# DCDC_4805.net
KiCad netlist of a schematic drawn in Altium Designer
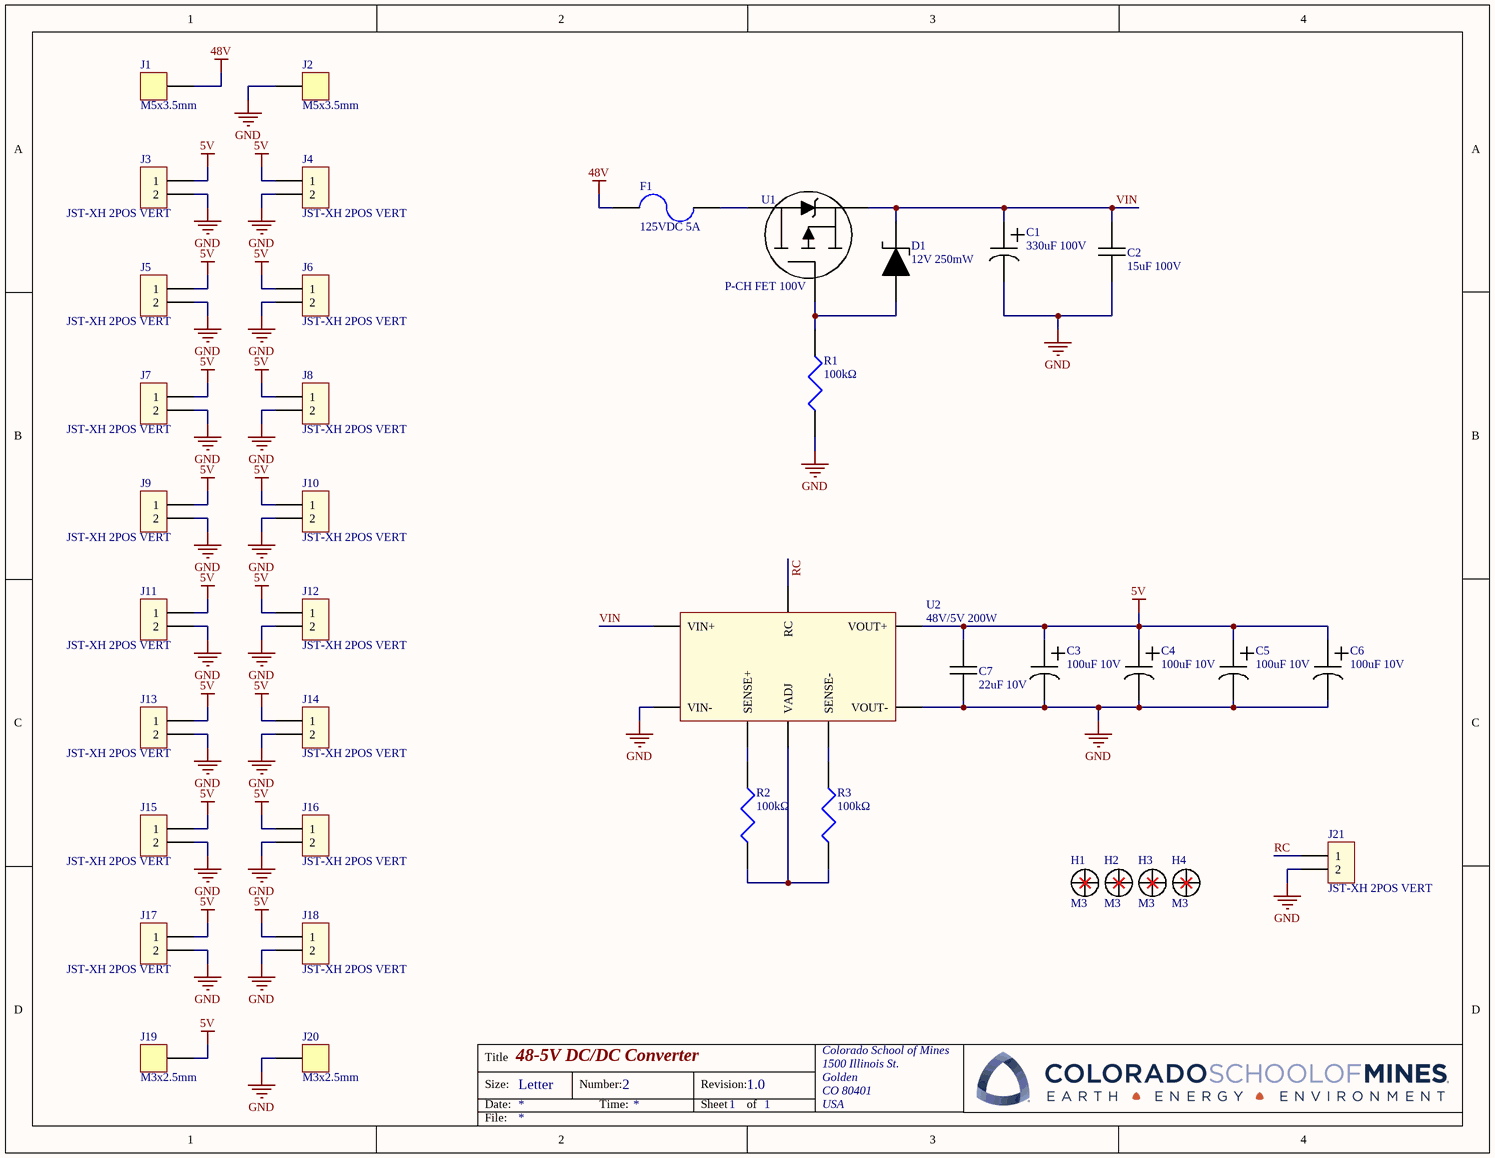
[diagram p0: DCDC_4805.SchDoc]

(export (version "E")
  (design (tool "Eeschema 10.0.6"))
  (components
    (comp (ref "C1")
      (value "330uF 100V")
      (footprint "EEV-FK2A331M")
      (description "Panasonic CAP ALUM 330UF 20% 100V SMD")
      (fields
        (field (name "PART NUMBER") "EEV-FK2A331M")
        (field (name "MANUFACTURER") "Panasonic Electronic Components")
      )
      (libsource (lib "MinesROV") (part "EEV-FK2A331M"))
    )
    (comp (ref "C2")
      (value "15uF 100V")
      (footprint "C2220M Generic")
      (description "TDK CAP CER 15UF 100V X7S 2220")
      (fields
        (field (name "PART NUMBER") "C5750X7S2A156M250KB")
        (field (name "MANUFACTURER") "TDK Corporation")
      )
      (libsource (lib "MinesROV") (part "C5750X7S2A156M250KB"))
    )
    (comp (ref "C3")
      (value "100uF 10V")
      (footprint "865080243007")
      (description "Wurth CAP ALUM POLY 100UF 20% 10V SMD")
      (fields (field (name "PART NUMBER") "865080243007") (field (name "MANUFACTURER") "Würth Elektronik"))
      (libsource (lib "MinesROV") (part "865080243007"))
    )
    (comp (ref "C4")
      (value "100uF 10V")
      (footprint "865080243007")
      (description "Wurth CAP ALUM POLY 100UF 20% 10V SMD")
      (fields (field (name "PART NUMBER") "865080243007") (field (name "MANUFACTURER") "Würth Elektronik"))
      (libsource (lib "MinesROV") (part "865080243007"))
    )
    (comp (ref "C5")
      (value "100uF 10V")
      (footprint "865080243007")
      (description "Wurth CAP ALUM POLY 100UF 20% 10V SMD")
      (fields (field (name "PART NUMBER") "865080243007") (field (name "MANUFACTURER") "Würth Elektronik"))
      (libsource (lib "MinesROV") (part "865080243007"))
    )
    (comp (ref "C6")
      (value "100uF 10V")
      (footprint "865080243007")
      (description "Wurth CAP ALUM POLY 100UF 20% 10V SMD")
      (fields (field (name "PART NUMBER") "865080243007") (field (name "MANUFACTURER") "Würth Elektronik"))
      (libsource (lib "MinesROV") (part "865080243007"))
    )
    (comp (ref "C7")
      (value "22uF 10V")
      (footprint "885012107011")
      (description "Wurth CAP CER 22UF 10V X5R 0805")
      (fields (field (name "PART NUMBER") "885012107011") (field (name "MANUFACTURER") "Würth Elektronik"))
      (libsource (lib "MinesROV") (part "885012107011"))
    )
    (comp (ref "D1")
      (value "12V 250mW")
      (footprint "BZX84-C12,235")
      (description "Nexperia DIODE ZENER 12V 250MW TO236AB")
      (fields (field (name "PART NUMBER") "BZX84-C12,235") (field (name "MANUFACTURER") "Nexperia"))
      (libsource (lib "MinesROV") (part "BZX84-C12,235"))
    )
    (comp (ref "F1")
      (value "125VDC 5A")
      (footprint "0154005.DRL")
      (description "Littelfuse FUSE BRD MNT 5A 125VAC/VDC 2SMD")
      (fields (field (name "MANUFACTURER") "Littelfuse") (field (name "PART NUMBER") "0456030.ER0154005.DRL"))
      (libsource (lib "MinesROV") (part "0154005.DRL"))
    )
    (comp (ref "H1")
      (value "M3")
      (footprint "M3_MOUNTING_HOLE")
      (description "MECHANICAL M3 Mounting Hole")
      (libsource (lib "MinesROV") (part "M3_Mounting_Hole"))
    )
    (comp (ref "H2")
      (value "M3")
      (footprint "M3_MOUNTING_HOLE")
      (description "MECHANICAL M3 Mounting Hole")
      (libsource (lib "MinesROV") (part "M3_Mounting_Hole"))
    )
    (comp (ref "H3")
      (value "M3")
      (footprint "M3_MOUNTING_HOLE")
      (description "MECHANICAL M3 Mounting Hole")
      (libsource (lib "MinesROV") (part "M3_Mounting_Hole"))
    )
    (comp (ref "H4")
      (value "M3")
      (footprint "M3_MOUNTING_HOLE")
      (description "MECHANICAL M3 Mounting Hole")
      (libsource (lib "MinesROV") (part "M3_Mounting_Hole"))
    )
    (comp (ref "J1")
      (value "M5x3.5mm")
      (footprint "74655095")
      (description "Wurth WP-THRBU REDCUBE THR internal through-hole thread, 10x10mm, M5x3.5mm, 8 pins, 85A")
      (fields
        (field (name "PART NUMBER") "74655095R")
        (field (name "MANUFACTURER") "Wurth Elektronik")
        (field (name "PUBLISHER") "Wurth Elektronik")
      )
      (libsource (lib "") (part "74655095R_1"))
    )
    (comp (ref "J2")
      (value "M5x3.5mm")
      (footprint "74655095")
      (description "Wurth WP-THRBU REDCUBE THR internal through-hole thread, 10x10mm, M5x3.5mm, 8 pins, 85A")
      (fields
        (field (name "PART NUMBER") "74655095R")
        (field (name "MANUFACTURER") "Wurth Elektronik")
        (field (name "PUBLISHER") "Wurth Elektronik")
      )
      (libsource (lib "MinesROV") (part "74655095R"))
    )
    (comp (ref "J3")
      (value "JST-XH 2POS VERT")
      (footprint "FP-B2B-XH-A_LF_SN-MFG")
      (description "JST XH CONN HEADER VERT 2POS 2.5MM")
      (fields (field (name "MANUFACTURER") "JST") (field (name "PART NUMBER") "B2B-XH-A(LF)(SN)"))
      (libsource (lib "MinesROV") (part "B2B-XH-A(LF)(SN)"))
    )
    (comp (ref "J4")
      (value "JST-XH 2POS VERT")
      (footprint "FP-B2B-XH-A_LF_SN-MFG")
      (description "JST XH CONN HEADER VERT 2POS 2.5MM")
      (fields (field (name "MANUFACTURER") "JST") (field (name "PART NUMBER") "B2B-XH-A(LF)(SN)"))
      (libsource (lib "") (part "B2B-XH-A(LF)(SN)_1"))
    )
    (comp (ref "J5")
      (value "JST-XH 2POS VERT")
      (footprint "FP-B2B-XH-A_LF_SN-MFG")
      (description "JST XH CONN HEADER VERT 2POS 2.5MM")
      (fields (field (name "MANUFACTURER") "JST") (field (name "PART NUMBER") "B2B-XH-A(LF)(SN)"))
      (libsource (lib "MinesROV") (part "B2B-XH-A(LF)(SN)"))
    )
    (comp (ref "J6")
      (value "JST-XH 2POS VERT")
      (footprint "FP-B2B-XH-A_LF_SN-MFG")
      (description "JST XH CONN HEADER VERT 2POS 2.5MM")
      (fields (field (name "MANUFACTURER") "JST") (field (name "PART NUMBER") "B2B-XH-A(LF)(SN)"))
      (libsource (lib "") (part "B2B-XH-A(LF)(SN)_1"))
    )
    (comp (ref "J7")
      (value "JST-XH 2POS VERT")
      (footprint "FP-B2B-XH-A_LF_SN-MFG")
      (description "JST XH CONN HEADER VERT 2POS 2.5MM")
      (fields (field (name "MANUFACTURER") "JST") (field (name "PART NUMBER") "B2B-XH-A(LF)(SN)"))
      (libsource (lib "MinesROV") (part "B2B-XH-A(LF)(SN)"))
    )
    (comp (ref "J8")
      (value "JST-XH 2POS VERT")
      (footprint "FP-B2B-XH-A_LF_SN-MFG")
      (description "JST XH CONN HEADER VERT 2POS 2.5MM")
      (fields (field (name "MANUFACTURER") "JST") (field (name "PART NUMBER") "B2B-XH-A(LF)(SN)"))
      (libsource (lib "") (part "B2B-XH-A(LF)(SN)_1"))
    )
    (comp (ref "J9")
      (value "JST-XH 2POS VERT")
      (footprint "FP-B2B-XH-A_LF_SN-MFG")
      (description "JST XH CONN HEADER VERT 2POS 2.5MM")
      (fields (field (name "MANUFACTURER") "JST") (field (name "PART NUMBER") "B2B-XH-A(LF)(SN)"))
      (libsource (lib "MinesROV") (part "B2B-XH-A(LF)(SN)"))
    )
    (comp (ref "J10")
      (value "JST-XH 2POS VERT")
      (footprint "FP-B2B-XH-A_LF_SN-MFG")
      (description "JST XH CONN HEADER VERT 2POS 2.5MM")
      (fields (field (name "MANUFACTURER") "JST") (field (name "PART NUMBER") "B2B-XH-A(LF)(SN)"))
      (libsource (lib "") (part "B2B-XH-A(LF)(SN)_1"))
    )
    (comp (ref "J11")
      (value "JST-XH 2POS VERT")
      (footprint "FP-B2B-XH-A_LF_SN-MFG")
      (description "JST XH CONN HEADER VERT 2POS 2.5MM")
      (fields (field (name "MANUFACTURER") "JST") (field (name "PART NUMBER") "B2B-XH-A(LF)(SN)"))
      (libsource (lib "MinesROV") (part "B2B-XH-A(LF)(SN)"))
    )
    (comp (ref "J12")
      (value "JST-XH 2POS VERT")
      (footprint "FP-B2B-XH-A_LF_SN-MFG")
      (description "JST XH CONN HEADER VERT 2POS 2.5MM")
      (fields (field (name "MANUFACTURER") "JST") (field (name "PART NUMBER") "B2B-XH-A(LF)(SN)"))
      (libsource (lib "") (part "B2B-XH-A(LF)(SN)_1"))
    )
    (comp (ref "J13")
      (value "JST-XH 2POS VERT")
      (footprint "FP-B2B-XH-A_LF_SN-MFG")
      (description "JST XH CONN HEADER VERT 2POS 2.5MM")
      (fields (field (name "MANUFACTURER") "JST") (field (name "PART NUMBER") "B2B-XH-A(LF)(SN)"))
      (libsource (lib "MinesROV") (part "B2B-XH-A(LF)(SN)"))
    )
    (comp (ref "J14")
      (value "JST-XH 2POS VERT")
      (footprint "FP-B2B-XH-A_LF_SN-MFG")
      (description "JST XH CONN HEADER VERT 2POS 2.5MM")
      (fields (field (name "MANUFACTURER") "JST") (field (name "PART NUMBER") "B2B-XH-A(LF)(SN)"))
      (libsource (lib "") (part "B2B-XH-A(LF)(SN)_1"))
    )
    (comp (ref "J15")
      (value "JST-XH 2POS VERT")
      (footprint "FP-B2B-XH-A_LF_SN-MFG")
      (description "JST XH CONN HEADER VERT 2POS 2.5MM")
      (fields (field (name "MANUFACTURER") "JST") (field (name "PART NUMBER") "B2B-XH-A(LF)(SN)"))
      (libsource (lib "MinesROV") (part "B2B-XH-A(LF)(SN)"))
    )
    (comp (ref "J16")
      (value "JST-XH 2POS VERT")
      (footprint "FP-B2B-XH-A_LF_SN-MFG")
      (description "JST XH CONN HEADER VERT 2POS 2.5MM")
      (fields (field (name "MANUFACTURER") "JST") (field (name "PART NUMBER") "B2B-XH-A(LF)(SN)"))
      (libsource (lib "") (part "B2B-XH-A(LF)(SN)_1"))
    )
    (comp (ref "J17")
      (value "JST-XH 2POS VERT")
      (footprint "FP-B2B-XH-A_LF_SN-MFG")
      (description "JST XH CONN HEADER VERT 2POS 2.5MM")
      (fields (field (name "MANUFACTURER") "JST") (field (name "PART NUMBER") "B2B-XH-A(LF)(SN)"))
      (libsource (lib "MinesROV") (part "B2B-XH-A(LF)(SN)"))
    )
    (comp (ref "J18")
      (value "JST-XH 2POS VERT")
      (footprint "FP-B2B-XH-A_LF_SN-MFG")
      (description "JST XH CONN HEADER VERT 2POS 2.5MM")
      (fields (field (name "MANUFACTURER") "JST") (field (name "PART NUMBER") "B2B-XH-A(LF)(SN)"))
      (libsource (lib "") (part "B2B-XH-A(LF)(SN)_1"))
    )
    (comp (ref "J19")
      (value "M3x2.5mm")
      (footprint "74650073")
      (description "Wurth WP-THRBU REDCUBE THR internal through-hole thread, 7x7mm, M3x2.5mm, 4 pins, 50A")
      (fields
        (field (name "PART NUMBER") "74650073R")
        (field (name "MANUFACTURER") "Wurth Elektronik")
        (field (name "PUBLISHER") "Wurth Elektronik")
      )
      (libsource (lib "") (part "74650073R_1"))
    )
    (comp (ref "J20")
      (value "M3x2.5mm")
      (footprint "74650073")
      (description "Wurth WP-THRBU REDCUBE THR internal through-hole thread, 7x7mm, M3x2.5mm, 4 pins, 50A")
      (fields
        (field (name "PART NUMBER") "74650073R")
        (field (name "MANUFACTURER") "Wurth Elektronik")
        (field (name "PUBLISHER") "Wurth Elektronik")
      )
      (libsource (lib "MinesROV") (part "74650073R"))
    )
    (comp (ref "J21")
      (value "JST-XH 2POS VERT")
      (footprint "FP-B2B-XH-A_LF_SN-MFG")
      (description "JST XH CONN HEADER VERT 2POS 2.5MM")
      (fields (field (name "MANUFACTURER") "JST") (field (name "PART NUMBER") "B2B-XH-A(LF)(SN)"))
      (libsource (lib "") (part "B2B-XH-A(LF)(SN)_1"))
    )
    (comp (ref "R1")
      (value "100kΩ")
      (footprint "RMCF0805")
      (description "Stackpole RES 100K OHM 1% 1/8W 0805")
      (fields
        (field (name "PART NUMBER") "RMCF0805FT100K")
        (field (name "MANUFACTURER") "Stackpole Electronics Inc")
      )
      (libsource (lib "MinesROV") (part "RMCF0805FT100K"))
    )
    (comp (ref "R2")
      (value "100kΩ")
      (footprint "RMCF0805")
      (description "Stackpole RES 100K OHM 1% 1/8W 0805")
      (fields
        (field (name "PART NUMBER") "RMCF0805FT100K")
        (field (name "MANUFACTURER") "Stackpole Electronics Inc")
      )
      (libsource (lib "MinesROV") (part "RMCF0805FT100K"))
    )
    (comp (ref "R3")
      (value "100kΩ")
      (footprint "RMCF0805")
      (description "Stackpole RES 100K OHM 1% 1/8W 0805")
      (fields
        (field (name "PART NUMBER") "RMCF0805FT100K")
        (field (name "MANUFACTURER") "Stackpole Electronics Inc")
      )
      (libsource (lib "MinesROV") (part "RMCF0805FT100K"))
    )
    (comp (ref "U1")
      (value "P-CH FET 100V")
      (footprint "IRF9530NSTRLPBF")
      (description "Infineon MOSFET P-CH 100V 14A D2PAK")
      (fields
        (field (name "MANUFACTURER") "Infineon Technologies")
        (field (name "PART NUMBER") "IRF9530NSTRLPBF")
      )
      (libsource (lib "MinesROV") (part "IRF9530NSTRLPBF"))
    )
    (comp (ref "U2")
      (value "48V/5V 200W")
      (footprint "PKB4211DPI")
      (description "Flex Power DC DC CONVERTER 5V 200W")
      (fields (field (name "MANUFACTURER") "Flex Power Modules") (field (name "PART NUMBER") "PKB4211DPI"))
      (libsource (lib "MinesROV") (part "PKB4211DPI"))
    )
  )
  (nets
    (net (code "1") (name "/RC") (class "Default")
      (node (ref "J21") (pin "1") (pinfunction "1_1") (pintype "passive"))
      (node (ref "U2") (pin "2") (pinfunction "RC_2") (pintype "passive"))
    )
    (net (code "2") (name "/VIN") (class "Default")
      (node (ref "C1") (pin "1") (pinfunction "1_1") (pintype "passive"))
      (node (ref "C2") (pin "2") (pinfunction "2_2") (pintype "passive"))
      (node (ref "D1") (pin "3") (pinfunction "3_3") (pintype "passive"))
      (node (ref "U1") (pin "3") (pinfunction "3_3") (pintype "passive"))
      (node (ref "U2") (pin "1") (pinfunction "VIN+_1") (pintype "passive"))
    )
    (net (code "3") (name "5V") (class "Default")
      (node (ref "C3") (pin "1") (pinfunction "1_1") (pintype "passive"))
      (node (ref "C4") (pin "1") (pinfunction "1_1") (pintype "passive"))
      (node (ref "C5") (pin "1") (pinfunction "1_1") (pintype "passive"))
      (node (ref "C6") (pin "1") (pinfunction "1_1") (pintype "passive"))
      (node (ref "C7") (pin "1") (pinfunction "1_1") (pintype "passive"))
      (node (ref "J10") (pin "1") (pinfunction "1_1") (pintype "passive"))
      (node (ref "J11") (pin "1") (pinfunction "1_1") (pintype "passive"))
      (node (ref "J12") (pin "1") (pinfunction "1_1") (pintype "passive"))
      (node (ref "J13") (pin "1") (pinfunction "1_1") (pintype "passive"))
      (node (ref "J14") (pin "1") (pinfunction "1_1") (pintype "passive"))
      (node (ref "J15") (pin "1") (pinfunction "1_1") (pintype "passive"))
      (node (ref "J16") (pin "1") (pinfunction "1_1") (pintype "passive"))
      (node (ref "J17") (pin "1") (pinfunction "1_1") (pintype "passive"))
      (node (ref "J18") (pin "1") (pinfunction "1_1") (pintype "passive"))
      (node (ref "J19") (pin "1") (pinfunction "1_1") (pintype "passive"))
      (node (ref "J3") (pin "1") (pinfunction "1_1") (pintype "passive"))
      (node (ref "J4") (pin "1") (pinfunction "1_1") (pintype "passive"))
      (node (ref "J5") (pin "1") (pinfunction "1_1") (pintype "passive"))
      (node (ref "J6") (pin "1") (pinfunction "1_1") (pintype "passive"))
      (node (ref "J7") (pin "1") (pinfunction "1_1") (pintype "passive"))
      (node (ref "J8") (pin "1") (pinfunction "1_1") (pintype "passive"))
      (node (ref "J9") (pin "1") (pinfunction "1_1") (pintype "passive"))
      (node (ref "U2") (pin "8") (pinfunction "VOUT+_8") (pintype "passive"))
    )
    (net (code "4") (name "48V") (class "Default")
      (node (ref "F1") (pin "1") (pinfunction "1_1") (pintype "passive"))
      (node (ref "J1") (pin "1") (pinfunction "1_1") (pintype "passive"))
    )
    (net (code "5") (name "GND") (class "Default")
      (node (ref "C1") (pin "2") (pinfunction "2_2") (pintype "passive"))
      (node (ref "C2") (pin "1") (pinfunction "1_1") (pintype "passive"))
      (node (ref "C3") (pin "2") (pinfunction "2_2") (pintype "passive"))
      (node (ref "C4") (pin "2") (pinfunction "2_2") (pintype "passive"))
      (node (ref "C5") (pin "2") (pinfunction "2_2") (pintype "passive"))
      (node (ref "C6") (pin "2") (pinfunction "2_2") (pintype "passive"))
      (node (ref "C7") (pin "2") (pinfunction "2_2") (pintype "passive"))
      (node (ref "J10") (pin "2") (pinfunction "2_2") (pintype "passive"))
      (node (ref "J11") (pin "2") (pinfunction "2_2") (pintype "passive"))
      (node (ref "J12") (pin "2") (pinfunction "2_2") (pintype "passive"))
      (node (ref "J13") (pin "2") (pinfunction "2_2") (pintype "passive"))
      (node (ref "J14") (pin "2") (pinfunction "2_2") (pintype "passive"))
      (node (ref "J15") (pin "2") (pinfunction "2_2") (pintype "passive"))
      (node (ref "J16") (pin "2") (pinfunction "2_2") (pintype "passive"))
      (node (ref "J17") (pin "2") (pinfunction "2_2") (pintype "passive"))
      (node (ref "J18") (pin "2") (pinfunction "2_2") (pintype "passive"))
      (node (ref "J2") (pin "1") (pinfunction "1_1") (pintype "passive"))
      (node (ref "J20") (pin "1") (pinfunction "1_1") (pintype "passive"))
      (node (ref "J21") (pin "2") (pinfunction "2_2") (pintype "passive"))
      (node (ref "J3") (pin "2") (pinfunction "2_2") (pintype "passive"))
      (node (ref "J4") (pin "2") (pinfunction "2_2") (pintype "passive"))
      (node (ref "J5") (pin "2") (pinfunction "2_2") (pintype "passive"))
      (node (ref "J6") (pin "2") (pinfunction "2_2") (pintype "passive"))
      (node (ref "J7") (pin "2") (pinfunction "2_2") (pintype "passive"))
      (node (ref "J8") (pin "2") (pinfunction "2_2") (pintype "passive"))
      (node (ref "J9") (pin "2") (pinfunction "2_2") (pintype "passive"))
      (node (ref "R1") (pin "1") (pinfunction "1_1") (pintype "passive"))
      (node (ref "U2") (pin "3") (pinfunction "VIN-_3") (pintype "passive"))
      (node (ref "U2") (pin "4") (pinfunction "VOUT-_4") (pintype "passive"))
    )
    (net (code "6") (name "Net-(D1-Pad1)") (class "Default")
      (node (ref "D1") (pin "1") (pinfunction "1_1") (pintype "passive"))
      (node (ref "R1") (pin "2") (pinfunction "2_2") (pintype "passive"))
      (node (ref "U1") (pin "1") (pinfunction "1_1") (pintype "passive"))
    )
    (net (code "7") (name "Net-(F1-Pad2)") (class "Default")
      (node (ref "F1") (pin "2") (pinfunction "2_2") (pintype "passive"))
      (node (ref "U1") (pin "4") (pinfunction "4_4") (pintype "passive"))
    )
    (net (code "8") (name "Net-(U2-SENSE+)") (class "Default")
      (node (ref "R2") (pin "2") (pinfunction "2_2") (pintype "passive"))
      (node (ref "U2") (pin "7") (pinfunction "SENSE+_7") (pintype "passive"))
    )
    (net (code "9") (name "Net-(U2-SENSE-)") (class "Default")
      (node (ref "R3") (pin "2") (pinfunction "2_2") (pintype "passive"))
      (node (ref "U2") (pin "5") (pinfunction "SENSE-_5") (pintype "passive"))
    )
    (net (code "10") (name "Net-(U2-VADJ)") (class "Default")
      (node (ref "R2") (pin "1") (pinfunction "1_1") (pintype "passive"))
      (node (ref "R3") (pin "1") (pinfunction "1_1") (pintype "passive"))
      (node (ref "U2") (pin "6") (pinfunction "VADJ_6") (pintype "passive"))
    )
    (net (code "11") (name "unconnected-(H1-Pad1)") (class "Default")
      (node (ref "H1") (pin "1") (pinfunction "1_1") (pintype "passive+no_connect"))
    )
    (net (code "12") (name "unconnected-(H2-Pad1)") (class "Default")
      (node (ref "H2") (pin "1") (pinfunction "1_1") (pintype "passive+no_connect"))
    )
    (net (code "13") (name "unconnected-(H3-Pad1)") (class "Default")
      (node (ref "H3") (pin "1") (pinfunction "1_1") (pintype "passive+no_connect"))
    )
    (net (code "14") (name "unconnected-(H4-Pad1)") (class "Default")
      (node (ref "H4") (pin "1") (pinfunction "1_1") (pintype "passive+no_connect"))
    )
  )
)
